# USB_Interface.net
KiCad netlist of a schematic drawn in EAGLE
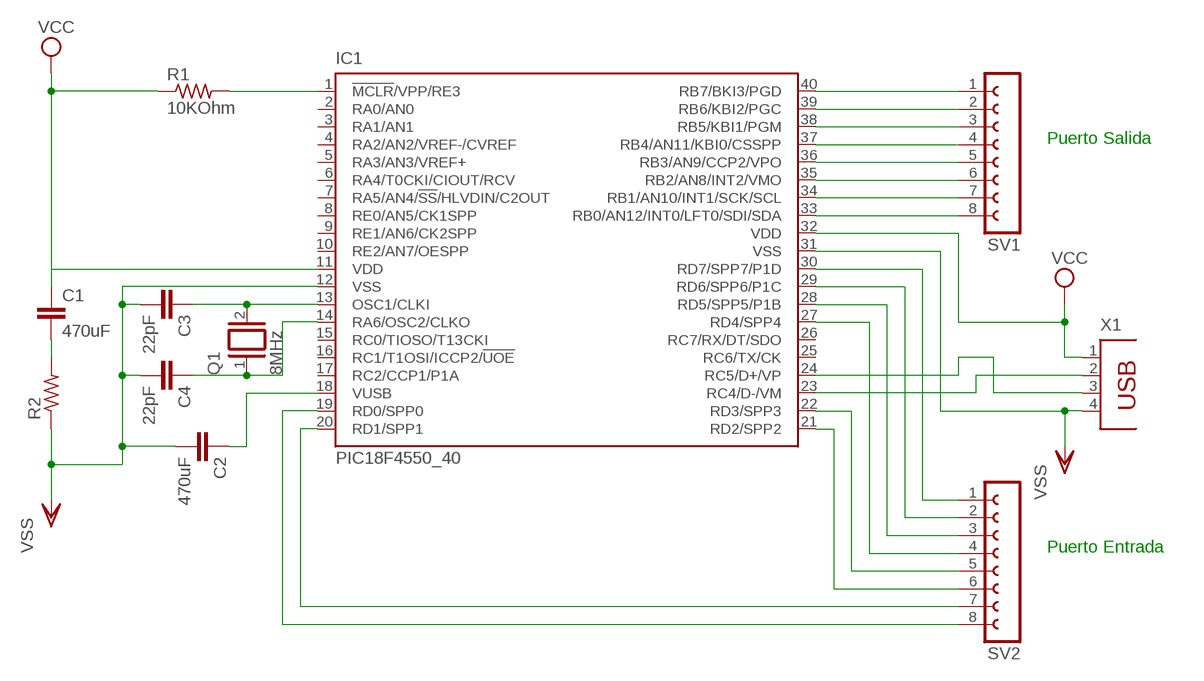
[diagram p0: schematic, sheet 1]

(export (version "E")
  (design (tool "Eeschema 10.0.6"))
  (components
    (comp (ref "C1")
      (value "470uF")
      (footprint "eagle-import:C2.5-4")
      (libsource (lib "eagle-import") (part "C2.5/4"))
    )
    (comp (ref "C2")
      (value "470uF")
      (footprint "eagle-import:C2.5-4")
      (libsource (lib "eagle-import") (part "C2.5/4"))
    )
    (comp (ref "C3")
      (value "22pF")
      (footprint "eagle-import:C2.5-4")
      (libsource (lib "eagle-import") (part "C2.5/4"))
    )
    (comp (ref "C4")
      (value "22pF")
      (footprint "eagle-import:C2.5-4")
      (libsource (lib "eagle-import") (part "C2.5/4"))
    )
    (comp (ref "IC1")
      (value "PIC18F4550_40")
      (footprint "eagle-import:DIL40")
      (fields (field (name "MF") "MICROCHIP") (field (name "MPN") "PIC18F4550-I/P"))
      (libsource (lib "eagle-import") (part "PIC18F4_40550"))
    )
    (comp (ref "Q1")
      (value "8MHz")
      (footprint "eagle-import:Q")
      (libsource (lib "eagle-import") (part "XTAL"))
    )
    (comp (ref "R1")
      (value "10KOhm")
      (footprint "eagle-import:0204V")
      (libsource (lib "eagle-import") (part "R-US_0204/2V"))
    )
    (comp (ref "R2")
      (value "R-US_0204/2V")
      (footprint "eagle-import:0204V")
      (libsource (lib "eagle-import") (part "R-US_0204/2V"))
    )
    (comp (ref "SV1")
      (value "FE08-1")
      (footprint "eagle-import:FE08")
      (libsource (lib "eagle-import") (part "FE08-1"))
    )
    (comp (ref "SV2")
      (value "FE08-1")
      (footprint "eagle-import:FE08")
      (libsource (lib "eagle-import") (part "FE08-1"))
    )
    (comp (ref "X1")
      (value "PN61729")
      (footprint "eagle-import:PN61729")
      (libsource (lib "eagle-import") (part "PN61729"))
    )
  )
  (nets
    (net (code "1") (name "Net-(C1-Pad2)") (class "Default")
      (node (ref "C1") (pin "2") (pinfunction "2_2") (pintype "passive"))
      (node (ref "R2") (pin "2") (pinfunction "2_2") (pintype "passive"))
    )
    (net (code "2") (name "Net-(IC1-OSC1{slash}CLKI)") (class "Default")
      (node (ref "C3") (pin "1") (pinfunction "1_1") (pintype "passive"))
      (node (ref "IC1") (pin "13") (pinfunction "OSC1/CLKI_13") (pintype "input"))
      (node (ref "Q1") (pin "2") (pinfunction "2_2") (pintype "passive"))
    )
    (net (code "3") (name "Net-(IC1-RA6{slash}OSC2{slash}CLKO)") (class "Default")
      (node (ref "C4") (pin "1") (pinfunction "1_1") (pintype "passive"))
      (node (ref "IC1") (pin "14") (pinfunction "RA6/OSC2/CLKO_14") (pintype "output"))
      (node (ref "Q1") (pin "1") (pinfunction "1_1") (pintype "passive"))
    )
    (net (code "4") (name "Net-(IC1-RB0{slash}AN12{slash}INT0{slash}LFT0{slash}SDI{slash}SDA)") (class "Default")
      (node (ref "IC1") (pin "33") (pinfunction "RB0/AN12/INT0/LFT0/SDI/SDA_33") (pintype "bidirectional"))
      (node (ref "SV1") (pin "8") (pinfunction "8_8") (pintype "passive"))
    )
    (net (code "5") (name "Net-(IC1-RB1{slash}AN10{slash}INT1{slash}SCK{slash}SCL)") (class "Default")
      (node (ref "IC1") (pin "34") (pinfunction "RB1/AN10/INT1/SCK/SCL_34") (pintype "bidirectional"))
      (node (ref "SV1") (pin "7") (pinfunction "7_7") (pintype "passive"))
    )
    (net (code "6") (name "Net-(IC1-RB2{slash}AN8{slash}INT2{slash}VMO)") (class "Default")
      (node (ref "IC1") (pin "35") (pinfunction "RB2/AN8/INT2/VMO_35") (pintype "bidirectional"))
      (node (ref "SV1") (pin "6") (pinfunction "6_6") (pintype "passive"))
    )
    (net (code "7") (name "Net-(IC1-RB3{slash}AN9{slash}CCP2{slash}VPO)") (class "Default")
      (node (ref "IC1") (pin "36") (pinfunction "RB3/AN9/CCP2/VPO_36") (pintype "bidirectional"))
      (node (ref "SV1") (pin "5") (pinfunction "5_5") (pintype "passive"))
    )
    (net (code "8") (name "Net-(IC1-RB4{slash}AN11{slash}KBI0{slash}CSSPP)") (class "Default")
      (node (ref "IC1") (pin "37") (pinfunction "RB4/AN11/KBI0/CSSPP_37") (pintype "bidirectional"))
      (node (ref "SV1") (pin "4") (pinfunction "4_4") (pintype "passive"))
    )
    (net (code "9") (name "Net-(IC1-RB5{slash}KBI1{slash}PGM)") (class "Default")
      (node (ref "IC1") (pin "38") (pinfunction "RB5/KBI1/PGM_38") (pintype "bidirectional"))
      (node (ref "SV1") (pin "3") (pinfunction "3_3") (pintype "passive"))
    )
    (net (code "10") (name "Net-(IC1-RB6{slash}KBI2{slash}PGC)") (class "Default")
      (node (ref "IC1") (pin "39") (pinfunction "RB6/KBI2/PGC_39") (pintype "bidirectional"))
      (node (ref "SV1") (pin "2") (pinfunction "2_2") (pintype "passive"))
    )
    (net (code "11") (name "Net-(IC1-RB7{slash}BKI3{slash}PGD)") (class "Default")
      (node (ref "IC1") (pin "40") (pinfunction "RB7/BKI3/PGD_40") (pintype "bidirectional"))
      (node (ref "SV1") (pin "1") (pinfunction "1_1") (pintype "passive"))
    )
    (net (code "12") (name "Net-(IC1-RC4{slash}D-{slash}VM)") (class "Default")
      (node (ref "IC1") (pin "23") (pinfunction "RC4/D-/VM_23") (pintype "bidirectional"))
      (node (ref "X1") (pin "2") (pinfunction "2_2") (pintype "passive"))
    )
    (net (code "13") (name "Net-(IC1-RC5{slash}D+{slash}VP)") (class "Default")
      (node (ref "IC1") (pin "24") (pinfunction "RC5/D+/VP_24") (pintype "bidirectional"))
      (node (ref "X1") (pin "3") (pinfunction "3_3") (pintype "passive"))
    )
    (net (code "14") (name "Net-(IC1-RD0{slash}SPP0)") (class "Default")
      (node (ref "IC1") (pin "19") (pinfunction "RD0/SPP0_19") (pintype "bidirectional"))
      (node (ref "SV2") (pin "8") (pinfunction "8_8") (pintype "passive"))
    )
    (net (code "15") (name "Net-(IC1-RD1{slash}SPP1)") (class "Default")
      (node (ref "IC1") (pin "20") (pinfunction "RD1/SPP1_20") (pintype "bidirectional"))
      (node (ref "SV2") (pin "7") (pinfunction "7_7") (pintype "passive"))
    )
    (net (code "16") (name "Net-(IC1-RD2{slash}SPP2)") (class "Default")
      (node (ref "IC1") (pin "21") (pinfunction "RD2/SPP2_21") (pintype "bidirectional"))
      (node (ref "SV2") (pin "6") (pinfunction "6_6") (pintype "passive"))
    )
    (net (code "17") (name "Net-(IC1-RD3{slash}SPP3)") (class "Default")
      (node (ref "IC1") (pin "22") (pinfunction "RD3/SPP3_22") (pintype "bidirectional"))
      (node (ref "SV2") (pin "5") (pinfunction "5_5") (pintype "passive"))
    )
    (net (code "18") (name "Net-(IC1-RD4{slash}SPP4)") (class "Default")
      (node (ref "IC1") (pin "27") (pinfunction "RD4/SPP4_27") (pintype "bidirectional"))
      (node (ref "SV2") (pin "4") (pinfunction "4_4") (pintype "passive"))
    )
    (net (code "19") (name "Net-(IC1-RD5{slash}SPP5{slash}P1B)") (class "Default")
      (node (ref "IC1") (pin "28") (pinfunction "RD5/SPP5/P1B_28") (pintype "bidirectional"))
      (node (ref "SV2") (pin "3") (pinfunction "3_3") (pintype "passive"))
    )
    (net (code "20") (name "Net-(IC1-RD6{slash}SPP6{slash}P1C)") (class "Default")
      (node (ref "IC1") (pin "29") (pinfunction "RD6/SPP6/P1C_29") (pintype "bidirectional"))
      (node (ref "SV2") (pin "2") (pinfunction "2_2") (pintype "passive"))
    )
    (net (code "21") (name "Net-(IC1-RD7{slash}SPP7{slash}P1D)") (class "Default")
      (node (ref "IC1") (pin "30") (pinfunction "RD7/SPP7/P1D_30") (pintype "bidirectional"))
      (node (ref "SV2") (pin "1") (pinfunction "1_1") (pintype "passive"))
    )
    (net (code "22") (name "Net-(IC1-VUSB)") (class "Default")
      (node (ref "C2") (pin "1") (pinfunction "1_1") (pintype "passive"))
      (node (ref "IC1") (pin "18") (pinfunction "VUSB_18") (pintype "bidirectional"))
    )
    (net (code "23") (name "Net-(IC1-~{MCLR}{slash}VPP{slash}RE3)") (class "Default")
      (node (ref "IC1") (pin "1") (pinfunction "~{MCLR}/VPP/RE3_1") (pintype "input"))
      (node (ref "R1") (pin "2") (pinfunction "2_2") (pintype "passive"))
    )
    (net (code "24") (name "VCC") (class "Default")
      (node (ref "C1") (pin "1") (pinfunction "1_1") (pintype "passive"))
      (node (ref "IC1") (pin "11") (pinfunction "VDD_11") (pintype "power_in"))
      (node (ref "IC1") (pin "32") (pinfunction "VDD_32") (pintype "power_in"))
      (node (ref "R1") (pin "1") (pinfunction "1_1") (pintype "passive"))
      (node (ref "X1") (pin "1") (pinfunction "1_1") (pintype "passive"))
    )
    (net (code "25") (name "VSS") (class "Default")
      (node (ref "C2") (pin "2") (pinfunction "2_2") (pintype "passive"))
      (node (ref "C3") (pin "2") (pinfunction "2_2") (pintype "passive"))
      (node (ref "C4") (pin "2") (pinfunction "2_2") (pintype "passive"))
      (node (ref "IC1") (pin "12") (pinfunction "VSS_12") (pintype "power_in"))
      (node (ref "IC1") (pin "31") (pinfunction "VSS_31") (pintype "power_in"))
      (node (ref "R2") (pin "1") (pinfunction "1_1") (pintype "passive"))
      (node (ref "X1") (pin "4") (pinfunction "4_4") (pintype "passive"))
    )
    (net (code "26") (name "unconnected-(IC1-RA0{slash}AN0-Pad2)") (class "Default")
      (node (ref "IC1") (pin "2") (pinfunction "RA0/AN0_2") (pintype "bidirectional"))
    )
    (net (code "27") (name "unconnected-(IC1-RA1{slash}AN1-Pad3)") (class "Default")
      (node (ref "IC1") (pin "3") (pinfunction "RA1/AN1_3") (pintype "bidirectional"))
    )
    (net (code "28") (name "unconnected-(IC1-RA2{slash}AN2{slash}VREF-{slash}CVREF-Pad4)") (class "Default")
      (node (ref "IC1") (pin "4") (pinfunction "RA2/AN2/VREF-/CVREF_4") (pintype "bidirectional"))
    )
    (net (code "29") (name "unconnected-(IC1-RA3{slash}AN3{slash}VREF+-Pad5)") (class "Default")
      (node (ref "IC1") (pin "5") (pinfunction "RA3/AN3/VREF+_5") (pintype "bidirectional"))
    )
    (net (code "30") (name "unconnected-(IC1-RA4{slash}T0CKI{slash}CIOUT{slash}RCV-Pad6)") (class "Default")
      (node (ref "IC1") (pin "6") (pinfunction "RA4/T0CKI/CIOUT/RCV_6") (pintype "bidirectional"))
    )
    (net (code "31") (name "unconnected-(IC1-RA5{slash}AN4{slash}~{SS}{slash}HLVDIN{slash}C2OUT-Pad7)") (class "Default")
      (node (ref "IC1") (pin "7") (pinfunction "RA5/AN4/~{SS}/HLVDIN/C2OUT_7") (pintype "bidirectional"))
    )
    (net (code "32") (name "unconnected-(IC1-RC0{slash}TIOSO{slash}T13CKI-Pad15)") (class "Default")
      (node (ref "IC1") (pin "15") (pinfunction "RC0/TIOSO/T13CKI_15") (pintype "bidirectional"))
    )
    (net (code "33") (name "unconnected-(IC1-RC1{slash}T1OSI{slash}ICCP2{slash}~{UOE}-Pad16)") (class "Default")
      (node (ref "IC1") (pin "16") (pinfunction "RC1/T1OSI/ICCP2/~{UOE}_16") (pintype "bidirectional"))
    )
    (net (code "34") (name "unconnected-(IC1-RC2{slash}CCP1{slash}P1A-Pad17)") (class "Default")
      (node (ref "IC1") (pin "17") (pinfunction "RC2/CCP1/P1A_17") (pintype "bidirectional"))
    )
    (net (code "35") (name "unconnected-(IC1-RC6{slash}TX{slash}CK-Pad25)") (class "Default")
      (node (ref "IC1") (pin "25") (pinfunction "RC6/TX/CK_25") (pintype "bidirectional"))
    )
    (net (code "36") (name "unconnected-(IC1-RC7{slash}RX{slash}DT{slash}SDO-Pad26)") (class "Default")
      (node (ref "IC1") (pin "26") (pinfunction "RC7/RX/DT/SDO_26") (pintype "bidirectional"))
    )
    (net (code "37") (name "unconnected-(IC1-RE0{slash}AN5{slash}CK1SPP-Pad8)") (class "Default")
      (node (ref "IC1") (pin "8") (pinfunction "RE0/AN5/CK1SPP_8") (pintype "bidirectional"))
    )
    (net (code "38") (name "unconnected-(IC1-RE1{slash}AN6{slash}CK2SPP-Pad9)") (class "Default")
      (node (ref "IC1") (pin "9") (pinfunction "RE1/AN6/CK2SPP_9") (pintype "bidirectional"))
    )
    (net (code "39") (name "unconnected-(IC1-RE2{slash}AN7{slash}OESPP-Pad10)") (class "Default")
      (node (ref "IC1") (pin "10") (pinfunction "RE2/AN7/OESPP_10") (pintype "bidirectional"))
    )
  )
)
